# MultiChannelFlex.net
KiCad netlist of a schematic drawn in Altium Designer
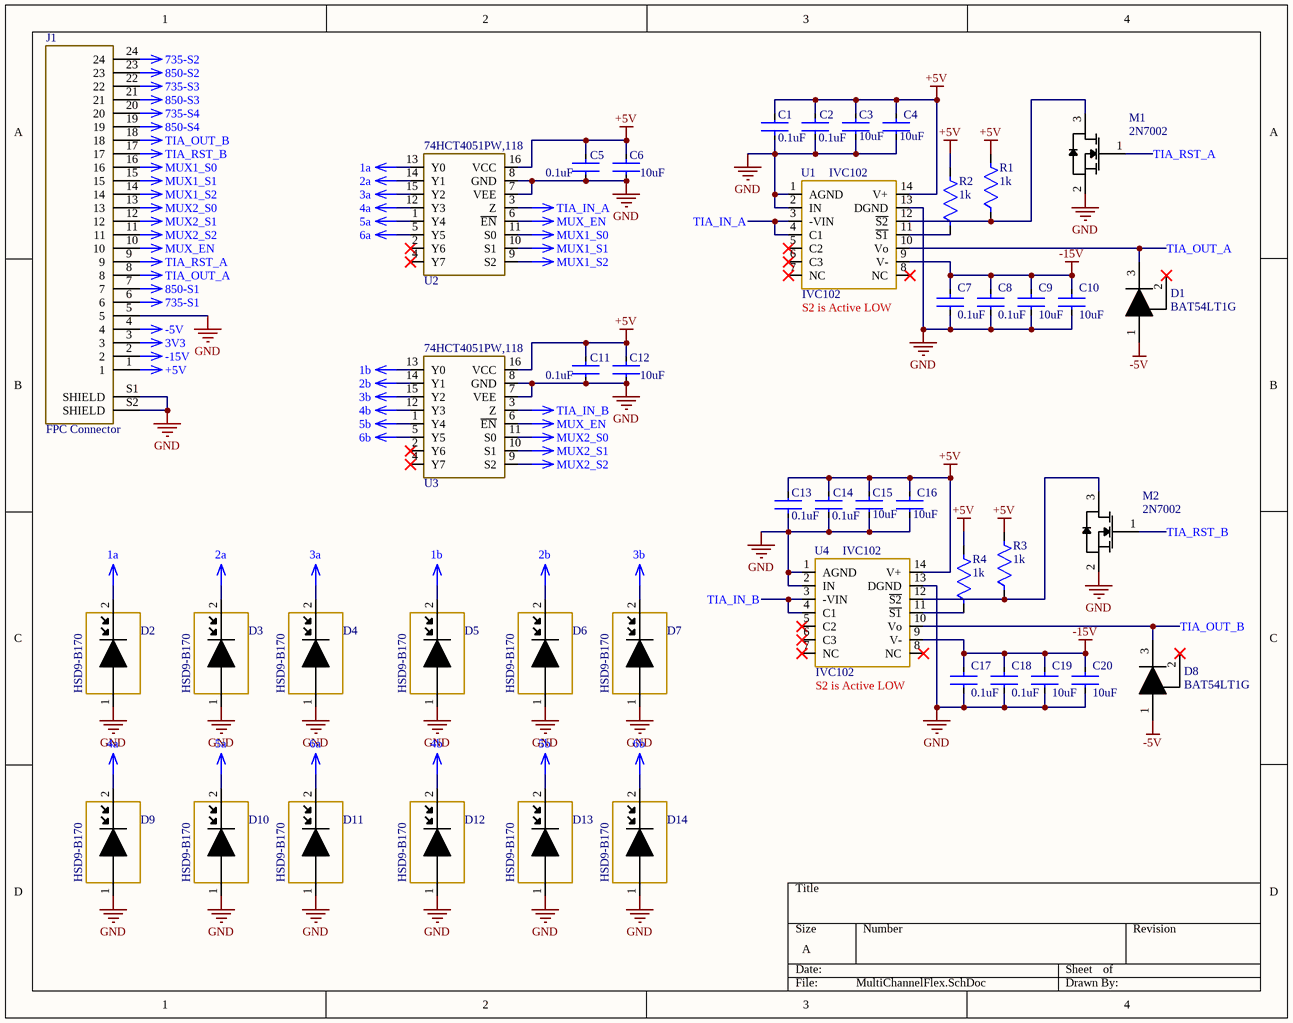
[diagram p0: MultiChannelFlex.SchDoc]

(export (version "E")
  (design (tool "Eeschema 10.0.6"))
  (components
    (comp (ref "C1")
      (value "0.1uF")
      (footprint "CAPC3216X180N")
      (description "1206")
      (fields (field (name "TOLERANCE") "0.1") (field (name "MANUFACTURER") "KEMET"))
      (libsource (lib "Single_Channel_fNIRS") (part "C1206C104K5RAC7210"))
    )
    (comp (ref "C2")
      (value "0.1uF")
      (footprint "CAPC3216X180N")
      (description "1206")
      (fields (field (name "TOLERANCE") "0.1") (field (name "MANUFACTURER") "KEMET"))
      (libsource (lib "Single_Channel_fNIRS") (part "C1206C104K5RAC7210"))
    )
    (comp (ref "C3")
      (value "10uF")
      (footprint "CAPC3216X180N")
      (description "1206")
      (libsource (lib "Single_Channel_fNIRS") (part "CL31B106KOHNNWE"))
    )
    (comp (ref "C4")
      (value "10uF")
      (footprint "CAPC3216X180N")
      (description "1206")
      (libsource (lib "Single_Channel_fNIRS") (part "CL31B106KOHNNWE"))
    )
    (comp (ref "C5")
      (value "0.1uF")
      (footprint "CAPC3216X180N")
      (description "1206")
      (fields (field (name "TOLERANCE") "0.1") (field (name "MANUFACTURER") "KEMET"))
      (libsource (lib "Single_Channel_fNIRS") (part "C1206C104K5RAC7210"))
    )
    (comp (ref "C6")
      (value "10uF")
      (footprint "CAPC3216X180N")
      (description "1206")
      (libsource (lib "Single_Channel_fNIRS") (part "CL31B106KOHNNWE"))
    )
    (comp (ref "C7")
      (value "0.1uF")
      (footprint "CAPC3216X180N")
      (description "1206")
      (fields (field (name "TOLERANCE") "0.1") (field (name "MANUFACTURER") "KEMET"))
      (libsource (lib "Single_Channel_fNIRS") (part "C1206C104K5RAC7210"))
    )
    (comp (ref "C8")
      (value "0.1uF")
      (footprint "CAPC3216X180N")
      (description "1206")
      (fields (field (name "TOLERANCE") "0.1") (field (name "MANUFACTURER") "KEMET"))
      (libsource (lib "Single_Channel_fNIRS") (part "C1206C104K5RAC7210"))
    )
    (comp (ref "C9")
      (value "10uF")
      (footprint "CAPC3216X180N")
      (description "1206")
      (libsource (lib "Single_Channel_fNIRS") (part "CL31B106KOHNNWE"))
    )
    (comp (ref "C10")
      (value "10uF")
      (footprint "CAPC3216X180N")
      (description "1206")
      (libsource (lib "Single_Channel_fNIRS") (part "CL31B106KOHNNWE"))
    )
    (comp (ref "C11")
      (value "0.1uF")
      (footprint "CAPC3216X180N")
      (description "1206")
      (fields (field (name "TOLERANCE") "0.1") (field (name "MANUFACTURER") "KEMET"))
      (libsource (lib "Single_Channel_fNIRS") (part "C1206C104K5RAC7210"))
    )
    (comp (ref "C12")
      (value "10uF")
      (footprint "CAPC3216X180N")
      (description "1206")
      (libsource (lib "Single_Channel_fNIRS") (part "CL31B106KOHNNWE"))
    )
    (comp (ref "C13")
      (value "0.1uF")
      (footprint "CAPC3216X180N")
      (description "1206")
      (fields (field (name "TOLERANCE") "0.1") (field (name "MANUFACTURER") "KEMET"))
      (libsource (lib "Single_Channel_fNIRS") (part "C1206C104K5RAC7210"))
    )
    (comp (ref "C14")
      (value "0.1uF")
      (footprint "CAPC3216X180N")
      (description "1206")
      (fields (field (name "TOLERANCE") "0.1") (field (name "MANUFACTURER") "KEMET"))
      (libsource (lib "Single_Channel_fNIRS") (part "C1206C104K5RAC7210"))
    )
    (comp (ref "C15")
      (value "10uF")
      (footprint "CAPC3216X180N")
      (description "1206")
      (libsource (lib "Single_Channel_fNIRS") (part "CL31B106KOHNNWE"))
    )
    (comp (ref "C16")
      (value "10uF")
      (footprint "CAPC3216X180N")
      (description "1206")
      (libsource (lib "Single_Channel_fNIRS") (part "CL31B106KOHNNWE"))
    )
    (comp (ref "C17")
      (value "0.1uF")
      (footprint "CAPC3216X180N")
      (description "1206")
      (fields (field (name "TOLERANCE") "0.1") (field (name "MANUFACTURER") "KEMET"))
      (libsource (lib "Single_Channel_fNIRS") (part "C1206C104K5RAC7210"))
    )
    (comp (ref "C18")
      (value "0.1uF")
      (footprint "CAPC3216X180N")
      (description "1206")
      (fields (field (name "TOLERANCE") "0.1") (field (name "MANUFACTURER") "KEMET"))
      (libsource (lib "Single_Channel_fNIRS") (part "C1206C104K5RAC7210"))
    )
    (comp (ref "C19")
      (value "10uF")
      (footprint "CAPC3216X180N")
      (description "1206")
      (libsource (lib "Single_Channel_fNIRS") (part "CL31B106KOHNNWE"))
    )
    (comp (ref "C20")
      (value "10uF")
      (footprint "CAPC3216X180N")
      (description "1206")
      (libsource (lib "Single_Channel_fNIRS") (part "CL31B106KOHNNWE"))
    )
    (comp (ref "D1")
      (value "BAT54LT1G")
      (footprint "BAT54LT1")
      (description "Schottky Barrier Diode, 3-Pin SOT-23, Pb-Free, Tape and Reel")
      (fields (field (name "MANUFACTURER") "On Semiconductor"))
      (libsource (lib "Single_Channel_fNIRS") (part "BAT54L"))
    )
    (comp (ref "D2")
      (value "HSD9-B170")
      (footprint "HSD9-B170")
      (libsource (lib "Single_Channel_fNIRS") (part "HSD9-B170"))
    )
    (comp (ref "D3")
      (value "HSD9-B170")
      (footprint "HSD9-B170")
      (libsource (lib "Single_Channel_fNIRS") (part "HSD9-B170"))
    )
    (comp (ref "D4")
      (value "HSD9-B170")
      (footprint "HSD9-B170")
      (libsource (lib "Single_Channel_fNIRS") (part "HSD9-B170"))
    )
    (comp (ref "D5")
      (value "HSD9-B170")
      (footprint "HSD9-B170")
      (libsource (lib "Single_Channel_fNIRS") (part "HSD9-B170"))
    )
    (comp (ref "D6")
      (value "HSD9-B170")
      (footprint "HSD9-B170")
      (libsource (lib "Single_Channel_fNIRS") (part "HSD9-B170"))
    )
    (comp (ref "D7")
      (value "HSD9-B170")
      (footprint "HSD9-B170")
      (libsource (lib "Single_Channel_fNIRS") (part "HSD9-B170"))
    )
    (comp (ref "D8")
      (value "BAT54LT1G")
      (footprint "BAT54LT1")
      (description "Schottky Barrier Diode, 3-Pin SOT-23, Pb-Free, Tape and Reel")
      (fields (field (name "MANUFACTURER") "On Semiconductor"))
      (libsource (lib "Single_Channel_fNIRS") (part "BAT54L"))
    )
    (comp (ref "D9")
      (value "HSD9-B170")
      (footprint "HSD9-B170")
      (libsource (lib "Single_Channel_fNIRS") (part "HSD9-B170"))
    )
    (comp (ref "D10")
      (value "HSD9-B170")
      (footprint "HSD9-B170")
      (libsource (lib "Single_Channel_fNIRS") (part "HSD9-B170"))
    )
    (comp (ref "D11")
      (value "HSD9-B170")
      (footprint "HSD9-B170")
      (libsource (lib "Single_Channel_fNIRS") (part "HSD9-B170"))
    )
    (comp (ref "D12")
      (value "HSD9-B170")
      (footprint "HSD9-B170")
      (libsource (lib "Single_Channel_fNIRS") (part "HSD9-B170"))
    )
    (comp (ref "D13")
      (value "HSD9-B170")
      (footprint "HSD9-B170")
      (libsource (lib "Single_Channel_fNIRS") (part "HSD9-B170"))
    )
    (comp (ref "D14")
      (value "HSD9-B170")
      (footprint "HSD9-B170")
      (libsource (lib "Single_Channel_fNIRS") (part "HSD9-B170"))
    )
    (comp (ref "J1")
      (value "FPC Connector")
      (footprint "TE_FPC")
      (description "24 Position FPC Connector Contacts, Bottom 0.020\" _0.50mm_ Surface Mount, Right Angle")
      (fields (field (name "MP") "2-1734592-4") (field (name "MF") "TE Connectivity"))
      (libsource (lib "MCU_Board_fNIRS") (part "2-1734592-4"))
    )
    (comp (ref "M1")
      (value "2N7002")
      (footprint "STM-SOT-23-3_V")
      (description "N-channel 60 V, 1.8 Ohm, 0.35 A STripFET(TM) II Power MOSFET, SOT23")
      (fields (field (name "MANUFACTURER") "STMicroelectronics"))
      (libsource (lib "Single_Channel_fNIRS") (part "2N7002-TP"))
    )
    (comp (ref "M2")
      (value "2N7002")
      (footprint "STM-SOT-23-3_V")
      (description "N-channel 60 V, 1.8 Ohm, 0.35 A STripFET(TM) II Power MOSFET, SOT23")
      (fields (field (name "MANUFACTURER") "STMicroelectronics"))
      (libsource (lib "Single_Channel_fNIRS") (part "2N7002-TP"))
    )
    (comp (ref "R1")
      (value "1k")
      (footprint "R1206")
      (description "1206 1kOhm")
      (libsource (lib "Single_Channel_fNIRS") (part "RT1206BRD071KL"))
    )
    (comp (ref "R2")
      (value "1k")
      (footprint "R1206")
      (description "1206 1kOhm")
      (libsource (lib "Single_Channel_fNIRS") (part "RT1206BRD071KL"))
    )
    (comp (ref "R3")
      (value "1k")
      (footprint "R1206")
      (description "1206 1kOhm")
      (libsource (lib "Single_Channel_fNIRS") (part "RT1206BRD071KL"))
    )
    (comp (ref "R4")
      (value "1k")
      (footprint "R1206")
      (description "1206 1kOhm")
      (libsource (lib "Single_Channel_fNIRS") (part "RT1206BRD071KL"))
    )
    (comp (ref "U1")
      (value "IVC102")
      (footprint "D0014A_M")
      (libsource (lib "Single_Channel_fNIRS") (part "IVC102"))
    )
    (comp (ref "U2")
      (value "8x1 Analog MUX TSSOP16")
      (footprint "TSSOP-16")
      (libsource (lib "MultiChannelFlex") (part "74HCT4051PW"))
    )
    (comp (ref "U3")
      (value "8x1 Analog MUX TSSOP16")
      (footprint "TSSOP-16")
      (libsource (lib "MultiChannelFlex") (part "74HCT4051PW"))
    )
    (comp (ref "U4")
      (value "IVC102")
      (footprint "D0014A_M")
      (libsource (lib "Single_Channel_fNIRS") (part "IVC102"))
    )
  )
  (nets
    (net (code "1") (name "+5V") (class "Default")
      (node (ref "C1") (pin "2") (pinfunction "2_2") (pintype "passive"))
      (node (ref "C11") (pin "1") (pinfunction "1_1") (pintype "passive"))
      (node (ref "C12") (pin "1") (pinfunction "1_1") (pintype "passive"))
      (node (ref "C13") (pin "2") (pinfunction "2_2") (pintype "passive"))
      (node (ref "C14") (pin "1") (pinfunction "1_1") (pintype "passive"))
      (node (ref "C15") (pin "1") (pinfunction "1_1") (pintype "passive"))
      (node (ref "C16") (pin "1") (pinfunction "1_1") (pintype "passive"))
      (node (ref "C2") (pin "1") (pinfunction "1_1") (pintype "passive"))
      (node (ref "C3") (pin "1") (pinfunction "1_1") (pintype "passive"))
      (node (ref "C4") (pin "1") (pinfunction "1_1") (pintype "passive"))
      (node (ref "C5") (pin "1") (pinfunction "1_1") (pintype "passive"))
      (node (ref "C6") (pin "1") (pinfunction "1_1") (pintype "passive"))
      (node (ref "J1") (pin "1") (pinfunction "1_1") (pintype "passive"))
      (node (ref "R1") (pin "2") (pinfunction "2_2") (pintype "passive"))
      (node (ref "R2") (pin "2") (pinfunction "2_2") (pintype "passive"))
      (node (ref "R3") (pin "2") (pinfunction "2_2") (pintype "passive"))
      (node (ref "R4") (pin "2") (pinfunction "2_2") (pintype "passive"))
      (node (ref "U1") (pin "14") (pinfunction "V+_14") (pintype "passive"))
      (node (ref "U2") (pin "16") (pinfunction "VCC_16") (pintype "passive"))
      (node (ref "U3") (pin "16") (pinfunction "VCC_16") (pintype "passive"))
      (node (ref "U4") (pin "14") (pinfunction "V+_14") (pintype "passive"))
    )
    (net (code "2") (name "-5V") (class "Default")
      (node (ref "D1") (pin "1") (pinfunction "A_1") (pintype "passive"))
      (node (ref "D8") (pin "1") (pinfunction "A_1") (pintype "passive"))
      (node (ref "J1") (pin "4") (pinfunction "4_4") (pintype "passive"))
    )
    (net (code "3") (name "-15V") (class "Default")
      (node (ref "C10") (pin "1") (pinfunction "1_1") (pintype "passive"))
      (node (ref "C17") (pin "1") (pinfunction "1_1") (pintype "passive"))
      (node (ref "C18") (pin "1") (pinfunction "1_1") (pintype "passive"))
      (node (ref "C19") (pin "1") (pinfunction "1_1") (pintype "passive"))
      (node (ref "C20") (pin "1") (pinfunction "1_1") (pintype "passive"))
      (node (ref "C7") (pin "1") (pinfunction "1_1") (pintype "passive"))
      (node (ref "C8") (pin "1") (pinfunction "1_1") (pintype "passive"))
      (node (ref "C9") (pin "1") (pinfunction "1_1") (pintype "passive"))
      (node (ref "J1") (pin "2") (pinfunction "2_2") (pintype "passive"))
      (node (ref "U1") (pin "9") (pinfunction "V-_9") (pintype "passive"))
      (node (ref "U4") (pin "9") (pinfunction "V-_9") (pintype "passive"))
    )
    (net (code "4") (name "1a") (class "Default")
      (node (ref "D2") (pin "2") (pinfunction "2_2") (pintype "passive"))
      (node (ref "U2") (pin "13") (pinfunction "Y0_13") (pintype "passive"))
    )
    (net (code "5") (name "1b") (class "Default")
      (node (ref "D5") (pin "2") (pinfunction "2_2") (pintype "passive"))
      (node (ref "U3") (pin "13") (pinfunction "Y0_13") (pintype "passive"))
    )
    (net (code "6") (name "2a") (class "Default")
      (node (ref "D3") (pin "2") (pinfunction "2_2") (pintype "passive"))
      (node (ref "U2") (pin "14") (pinfunction "Y1_14") (pintype "passive"))
    )
    (net (code "7") (name "2b") (class "Default")
      (node (ref "D6") (pin "2") (pinfunction "2_2") (pintype "passive"))
      (node (ref "U3") (pin "14") (pinfunction "Y1_14") (pintype "passive"))
    )
    (net (code "8") (name "3V3") (class "Default")
      (node (ref "J1") (pin "3") (pinfunction "3_3") (pintype "passive"))
    )
    (net (code "9") (name "3a") (class "Default")
      (node (ref "D4") (pin "2") (pinfunction "2_2") (pintype "passive"))
      (node (ref "U2") (pin "15") (pinfunction "Y2_15") (pintype "passive"))
    )
    (net (code "10") (name "3b") (class "Default")
      (node (ref "D7") (pin "2") (pinfunction "2_2") (pintype "passive"))
      (node (ref "U3") (pin "15") (pinfunction "Y2_15") (pintype "passive"))
    )
    (net (code "11") (name "4a") (class "Default")
      (node (ref "D9") (pin "2") (pinfunction "2_2") (pintype "passive"))
      (node (ref "U2") (pin "12") (pinfunction "Y3_12") (pintype "passive"))
    )
    (net (code "12") (name "4b") (class "Default")
      (node (ref "D12") (pin "2") (pinfunction "2_2") (pintype "passive"))
      (node (ref "U3") (pin "12") (pinfunction "Y3_12") (pintype "passive"))
    )
    (net (code "13") (name "5a") (class "Default")
      (node (ref "D10") (pin "2") (pinfunction "2_2") (pintype "passive"))
      (node (ref "U2") (pin "1") (pinfunction "Y4_1") (pintype "passive"))
    )
    (net (code "14") (name "5b") (class "Default")
      (node (ref "D13") (pin "2") (pinfunction "2_2") (pintype "passive"))
      (node (ref "U3") (pin "1") (pinfunction "Y4_1") (pintype "passive"))
    )
    (net (code "15") (name "6a") (class "Default")
      (node (ref "D11") (pin "2") (pinfunction "2_2") (pintype "passive"))
      (node (ref "U2") (pin "5") (pinfunction "Y5_5") (pintype "passive"))
    )
    (net (code "16") (name "6b") (class "Default")
      (node (ref "D14") (pin "2") (pinfunction "2_2") (pintype "passive"))
      (node (ref "U3") (pin "5") (pinfunction "Y5_5") (pintype "passive"))
    )
    (net (code "17") (name "735-S1") (class "Default")
      (node (ref "J1") (pin "6") (pinfunction "6_6") (pintype "passive"))
    )
    (net (code "18") (name "735-S2") (class "Default")
      (node (ref "J1") (pin "24") (pinfunction "24_24") (pintype "passive"))
    )
    (net (code "19") (name "735-S3") (class "Default")
      (node (ref "J1") (pin "22") (pinfunction "22_22") (pintype "passive"))
    )
    (net (code "20") (name "735-S4") (class "Default")
      (node (ref "J1") (pin "20") (pinfunction "20_20") (pintype "passive"))
    )
    (net (code "21") (name "850-S1") (class "Default")
      (node (ref "J1") (pin "7") (pinfunction "7_7") (pintype "passive"))
    )
    (net (code "22") (name "850-S2") (class "Default")
      (node (ref "J1") (pin "23") (pinfunction "23_23") (pintype "passive"))
    )
    (net (code "23") (name "850-S3") (class "Default")
      (node (ref "J1") (pin "21") (pinfunction "21_21") (pintype "passive"))
    )
    (net (code "24") (name "850-S4") (class "Default")
      (node (ref "J1") (pin "19") (pinfunction "19_19") (pintype "passive"))
    )
    (net (code "25") (name "GND") (class "Default")
      (node (ref "C1") (pin "1") (pinfunction "1_1") (pintype "passive"))
      (node (ref "C10") (pin "2") (pinfunction "2_2") (pintype "passive"))
      (node (ref "C11") (pin "2") (pinfunction "2_2") (pintype "passive"))
      (node (ref "C12") (pin "2") (pinfunction "2_2") (pintype "passive"))
      (node (ref "C13") (pin "1") (pinfunction "1_1") (pintype "passive"))
      (node (ref "C14") (pin "2") (pinfunction "2_2") (pintype "passive"))
      (node (ref "C15") (pin "2") (pinfunction "2_2") (pintype "passive"))
      (node (ref "C16") (pin "2") (pinfunction "2_2") (pintype "passive"))
      (node (ref "C17") (pin "2") (pinfunction "2_2") (pintype "passive"))
      (node (ref "C18") (pin "2") (pinfunction "2_2") (pintype "passive"))
      (node (ref "C19") (pin "2") (pinfunction "2_2") (pintype "passive"))
      (node (ref "C2") (pin "2") (pinfunction "2_2") (pintype "passive"))
      (node (ref "C20") (pin "2") (pinfunction "2_2") (pintype "passive"))
      (node (ref "C3") (pin "2") (pinfunction "2_2") (pintype "passive"))
      (node (ref "C4") (pin "2") (pinfunction "2_2") (pintype "passive"))
      (node (ref "C5") (pin "2") (pinfunction "2_2") (pintype "passive"))
      (node (ref "C6") (pin "2") (pinfunction "2_2") (pintype "passive"))
      (node (ref "C7") (pin "2") (pinfunction "2_2") (pintype "passive"))
      (node (ref "C8") (pin "2") (pinfunction "2_2") (pintype "passive"))
      (node (ref "C9") (pin "2") (pinfunction "2_2") (pintype "passive"))
      (node (ref "D10") (pin "1") (pinfunction "1_1") (pintype "passive"))
      (node (ref "D11") (pin "1") (pinfunction "1_1") (pintype "passive"))
      (node (ref "D12") (pin "1") (pinfunction "1_1") (pintype "passive"))
      (node (ref "D13") (pin "1") (pinfunction "1_1") (pintype "passive"))
      (node (ref "D14") (pin "1") (pinfunction "1_1") (pintype "passive"))
      (node (ref "D2") (pin "1") (pinfunction "1_1") (pintype "passive"))
      (node (ref "D3") (pin "1") (pinfunction "1_1") (pintype "passive"))
      (node (ref "D4") (pin "1") (pinfunction "1_1") (pintype "passive"))
      (node (ref "D5") (pin "1") (pinfunction "1_1") (pintype "passive"))
      (node (ref "D6") (pin "1") (pinfunction "1_1") (pintype "passive"))
      (node (ref "D7") (pin "1") (pinfunction "1_1") (pintype "passive"))
      (node (ref "D9") (pin "1") (pinfunction "1_1") (pintype "passive"))
      (node (ref "J1") (pin "5") (pinfunction "5_5") (pintype "passive"))
      (node (ref "J1") (pin "S1") (pinfunction "SHIELD_S1") (pintype "passive"))
      (node (ref "J1") (pin "S2") (pinfunction "SHIELD_S2") (pintype "passive"))
      (node (ref "M1") (pin "2") (pinfunction "S_2") (pintype "passive"))
      (node (ref "M2") (pin "2") (pinfunction "S_2") (pintype "passive"))
      (node (ref "U1") (pin "1") (pinfunction "AGND_1") (pintype "passive"))
      (node (ref "U1") (pin "13") (pinfunction "DGND_13") (pintype "passive"))
      (node (ref "U1") (pin "2") (pinfunction "IN_2") (pintype "passive"))
      (node (ref "U2") (pin "7") (pinfunction "VEE_7") (pintype "passive"))
      (node (ref "U2") (pin "8") (pinfunction "GND_8") (pintype "passive"))
      (node (ref "U3") (pin "7") (pinfunction "VEE_7") (pintype "passive"))
      (node (ref "U3") (pin "8") (pinfunction "GND_8") (pintype "passive"))
      (node (ref "U4") (pin "1") (pinfunction "AGND_1") (pintype "passive"))
      (node (ref "U4") (pin "13") (pinfunction "DGND_13") (pintype "passive"))
      (node (ref "U4") (pin "2") (pinfunction "IN_2") (pintype "passive"))
    )
    (net (code "26") (name "MUX1_S0") (class "Default")
      (node (ref "J1") (pin "16") (pinfunction "16_16") (pintype "passive"))
      (node (ref "U2") (pin "11") (pinfunction "S0_11") (pintype "passive"))
    )
    (net (code "27") (name "MUX1_S1") (class "Default")
      (node (ref "J1") (pin "15") (pinfunction "15_15") (pintype "passive"))
      (node (ref "U2") (pin "10") (pinfunction "S1_10") (pintype "passive"))
    )
    (net (code "28") (name "MUX1_S2") (class "Default")
      (node (ref "J1") (pin "14") (pinfunction "14_14") (pintype "passive"))
      (node (ref "U2") (pin "9") (pinfunction "S2_9") (pintype "passive"))
    )
    (net (code "29") (name "MUX2_S0") (class "Default")
      (node (ref "J1") (pin "13") (pinfunction "13_13") (pintype "passive"))
      (node (ref "U3") (pin "11") (pinfunction "S0_11") (pintype "passive"))
    )
    (net (code "30") (name "MUX2_S1") (class "Default")
      (node (ref "J1") (pin "12") (pinfunction "12_12") (pintype "passive"))
      (node (ref "U3") (pin "10") (pinfunction "S1_10") (pintype "passive"))
    )
    (net (code "31") (name "MUX2_S2") (class "Default")
      (node (ref "J1") (pin "11") (pinfunction "11_11") (pintype "passive"))
      (node (ref "U3") (pin "9") (pinfunction "S2_9") (pintype "passive"))
    )
    (net (code "32") (name "MUX_EN") (class "Default")
      (node (ref "J1") (pin "10") (pinfunction "10_10") (pintype "passive"))
      (node (ref "U2") (pin "6") (pinfunction "~{EN}_6") (pintype "passive"))
      (node (ref "U3") (pin "6") (pinfunction "~{EN}_6") (pintype "passive"))
    )
    (net (code "33") (name "Net-(M1-D)") (class "Default")
      (node (ref "M1") (pin "3") (pinfunction "D_3") (pintype "passive"))
      (node (ref "R1") (pin "1") (pinfunction "1_1") (pintype "passive"))
      (node (ref "U1") (pin "12") (pinfunction "~{S2}_12") (pintype "passive"))
    )
    (net (code "34") (name "Net-(M2-D)") (class "Default")
      (node (ref "M2") (pin "3") (pinfunction "D_3") (pintype "passive"))
      (node (ref "R3") (pin "1") (pinfunction "1_1") (pintype "passive"))
      (node (ref "U4") (pin "12") (pinfunction "~{S2}_12") (pintype "passive"))
    )
    (net (code "35") (name "Net-(U1-~{S1})") (class "Default")
      (node (ref "R2") (pin "1") (pinfunction "1_1") (pintype "passive"))
      (node (ref "U1") (pin "11") (pinfunction "~{S1}_11") (pintype "passive"))
    )
    (net (code "36") (name "Net-(U4-~{S1})") (class "Default")
      (node (ref "R4") (pin "1") (pinfunction "1_1") (pintype "passive"))
      (node (ref "U4") (pin "11") (pinfunction "~{S1}_11") (pintype "passive"))
    )
    (net (code "37") (name "TIA_IN_A") (class "Default")
      (node (ref "U1") (pin "3") (pinfunction "-VIN_3") (pintype "passive"))
      (node (ref "U1") (pin "4") (pinfunction "C1_4") (pintype "passive"))
      (node (ref "U2") (pin "3") (pinfunction "Z_3") (pintype "passive"))
    )
    (net (code "38") (name "TIA_IN_B") (class "Default")
      (node (ref "U3") (pin "3") (pinfunction "Z_3") (pintype "passive"))
      (node (ref "U4") (pin "3") (pinfunction "-VIN_3") (pintype "passive"))
      (node (ref "U4") (pin "4") (pinfunction "C1_4") (pintype "passive"))
    )
    (net (code "39") (name "TIA_OUT_A") (class "Default")
      (node (ref "D1") (pin "3") (pinfunction "K_3") (pintype "passive"))
      (node (ref "J1") (pin "8") (pinfunction "8_8") (pintype "passive"))
      (node (ref "U1") (pin "10") (pinfunction "Vo_10") (pintype "passive"))
    )
    (net (code "40") (name "TIA_OUT_B") (class "Default")
      (node (ref "D8") (pin "3") (pinfunction "K_3") (pintype "passive"))
      (node (ref "J1") (pin "18") (pinfunction "18_18") (pintype "passive"))
      (node (ref "U4") (pin "10") (pinfunction "Vo_10") (pintype "passive"))
    )
    (net (code "41") (name "TIA_RST_A") (class "Default")
      (node (ref "J1") (pin "9") (pinfunction "9_9") (pintype "passive"))
      (node (ref "M1") (pin "1") (pinfunction "G_1") (pintype "passive"))
    )
    (net (code "42") (name "TIA_RST_B") (class "Default")
      (node (ref "J1") (pin "17") (pinfunction "17_17") (pintype "passive"))
      (node (ref "M2") (pin "1") (pinfunction "G_1") (pintype "passive"))
    )
    (net (code "43") (name "unconnected-(D1-NC-Pad2)") (class "Default")
      (node (ref "D1") (pin "2") (pinfunction "NC_2") (pintype "passive+no_connect"))
    )
    (net (code "44") (name "unconnected-(D8-NC-Pad2)") (class "Default")
      (node (ref "D8") (pin "2") (pinfunction "NC_2") (pintype "passive+no_connect"))
    )
    (net (code "45") (name "unconnected-(U1-C2-Pad5)") (class "Default")
      (node (ref "U1") (pin "5") (pinfunction "C2_5") (pintype "passive+no_connect"))
    )
    (net (code "46") (name "unconnected-(U1-C3-Pad6)") (class "Default")
      (node (ref "U1") (pin "6") (pinfunction "C3_6") (pintype "passive+no_connect"))
    )
    (net (code "47") (name "unconnected-(U1-NC-Pad7)") (class "Default")
      (node (ref "U1") (pin "7") (pinfunction "NC_7") (pintype "passive+no_connect"))
    )
    (net (code "48") (name "unconnected-(U1-NC-Pad8)") (class "Default")
      (node (ref "U1") (pin "8") (pinfunction "NC_8") (pintype "passive+no_connect"))
    )
    (net (code "49") (name "unconnected-(U2-Y6-Pad2)") (class "Default")
      (node (ref "U2") (pin "2") (pinfunction "Y6_2") (pintype "passive+no_connect"))
    )
    (net (code "50") (name "unconnected-(U2-Y7-Pad4)") (class "Default")
      (node (ref "U2") (pin "4") (pinfunction "Y7_4") (pintype "passive+no_connect"))
    )
    (net (code "51") (name "unconnected-(U3-Y6-Pad2)") (class "Default")
      (node (ref "U3") (pin "2") (pinfunction "Y6_2") (pintype "passive+no_connect"))
    )
    (net (code "52") (name "unconnected-(U3-Y7-Pad4)") (class "Default")
      (node (ref "U3") (pin "4") (pinfunction "Y7_4") (pintype "passive+no_connect"))
    )
    (net (code "53") (name "unconnected-(U4-C2-Pad5)") (class "Default")
      (node (ref "U4") (pin "5") (pinfunction "C2_5") (pintype "passive+no_connect"))
    )
    (net (code "54") (name "unconnected-(U4-C3-Pad6)") (class "Default")
      (node (ref "U4") (pin "6") (pinfunction "C3_6") (pintype "passive+no_connect"))
    )
    (net (code "55") (name "unconnected-(U4-NC-Pad7)") (class "Default")
      (node (ref "U4") (pin "7") (pinfunction "NC_7") (pintype "passive+no_connect"))
    )
    (net (code "56") (name "unconnected-(U4-NC-Pad8)") (class "Default")
      (node (ref "U4") (pin "8") (pinfunction "NC_8") (pintype "passive+no_connect"))
    )
  )
)
